# SHIELDV1_NANO.net
KiCad netlist of a schematic drawn in EAGLE
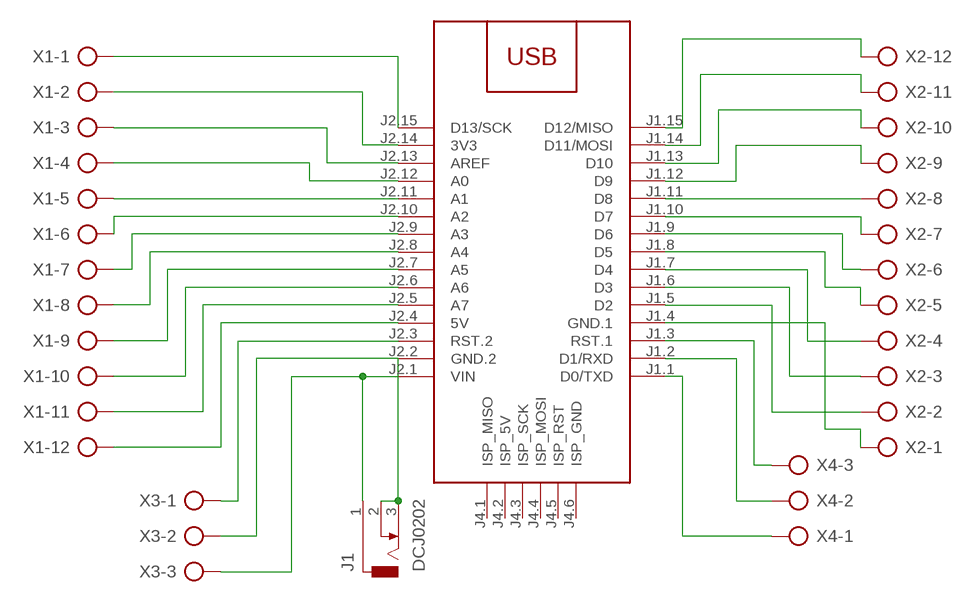
[diagram p0: schematic, sheet 1]

(export (version "E")
  (design (tool "Eeschema 10.0.6"))
  (components
    (comp (ref "J1")
      (value "DCJ0202")
      (footprint "eagle-import:DCJ0202")
      (libsource (lib "eagle-import") (part "DCJ0202"))
    )
    (comp (ref "M1")
      (value "ARDUINO-NANO-3.0#ISP")
      (footprint "eagle-import:ARDUINO-NANO-3.0#ISP")
      (libsource (lib "eagle-import") (part "ARDUINO-NANO-3.0#ISP"))
    )
    (comp (ref "X1")
      (value "AK500/12-H")
      (footprint "eagle-import:AK500_12-H")
      (libsource (lib "eagle-import") (part "AK500/12-H"))
    )
    (comp (ref "X2")
      (value "AK500/12-H")
      (footprint "eagle-import:AK500_12-H")
      (libsource (lib "eagle-import") (part "AK500/12-H"))
    )
    (comp (ref "X3")
      (value "AK500/3")
      (footprint "eagle-import:AK500_3")
      (libsource (lib "eagle-import") (part "AK500/3"))
    )
    (comp (ref "X4")
      (value "AK500/3")
      (footprint "eagle-import:AK500_3")
      (libsource (lib "eagle-import") (part "AK500/3"))
    )
  )
  (nets
    (net (code "1") (name "Net-(M1-3V3)") (class "Default")
      (node (ref "M1") (pin "J2.14") (pinfunction "3V3_J2.14") (pintype "power_in"))
      (node (ref "X1") (pin "2") (pinfunction "KL_2") (pintype "passive"))
    )
    (net (code "2") (name "Net-(M1-5V)") (class "Default")
      (node (ref "M1") (pin "J2.4") (pinfunction "5V_J2.4") (pintype "power_in"))
      (node (ref "X1") (pin "12") (pinfunction "KL_12") (pintype "passive"))
    )
    (net (code "3") (name "Net-(M1-A0)") (class "Default")
      (node (ref "M1") (pin "J2.12") (pinfunction "A0_J2.12") (pintype "bidirectional"))
      (node (ref "X1") (pin "4") (pinfunction "KL_4") (pintype "passive"))
    )
    (net (code "4") (name "Net-(M1-A1)") (class "Default")
      (node (ref "M1") (pin "J2.11") (pinfunction "A1_J2.11") (pintype "bidirectional"))
      (node (ref "X1") (pin "5") (pinfunction "KL_5") (pintype "passive"))
    )
    (net (code "5") (name "Net-(M1-A2)") (class "Default")
      (node (ref "M1") (pin "J2.10") (pinfunction "A2_J2.10") (pintype "bidirectional"))
      (node (ref "X1") (pin "6") (pinfunction "KL_6") (pintype "passive"))
    )
    (net (code "6") (name "Net-(M1-A3)") (class "Default")
      (node (ref "M1") (pin "J2.9") (pinfunction "A3_J2.9") (pintype "bidirectional"))
      (node (ref "X1") (pin "7") (pinfunction "KL_7") (pintype "passive"))
    )
    (net (code "7") (name "Net-(M1-A4)") (class "Default")
      (node (ref "M1") (pin "J2.8") (pinfunction "A4_J2.8") (pintype "bidirectional"))
      (node (ref "X1") (pin "8") (pinfunction "KL_8") (pintype "passive"))
    )
    (net (code "8") (name "Net-(M1-A5)") (class "Default")
      (node (ref "M1") (pin "J2.7") (pinfunction "A5_J2.7") (pintype "bidirectional"))
      (node (ref "X1") (pin "9") (pinfunction "KL_9") (pintype "passive"))
    )
    (net (code "9") (name "Net-(M1-A6)") (class "Default")
      (node (ref "M1") (pin "J2.6") (pinfunction "A6_J2.6") (pintype "bidirectional"))
      (node (ref "X1") (pin "10") (pinfunction "KL_10") (pintype "passive"))
    )
    (net (code "10") (name "Net-(M1-A7)") (class "Default")
      (node (ref "M1") (pin "J2.5") (pinfunction "A7_J2.5") (pintype "bidirectional"))
      (node (ref "X1") (pin "11") (pinfunction "KL_11") (pintype "passive"))
    )
    (net (code "11") (name "Net-(M1-AREF)") (class "Default")
      (node (ref "M1") (pin "J2.13") (pinfunction "AREF_J2.13") (pintype "bidirectional"))
      (node (ref "X1") (pin "3") (pinfunction "KL_3") (pintype "passive"))
    )
    (net (code "12") (name "Net-(M1-D0{slash}TXD)") (class "Default")
      (node (ref "M1") (pin "J1.1") (pinfunction "D0/TXD_J1.1") (pintype "bidirectional"))
      (node (ref "X4") (pin "1") (pinfunction "KL_1") (pintype "passive"))
    )
    (net (code "13") (name "Net-(M1-D1{slash}RXD)") (class "Default")
      (node (ref "M1") (pin "J1.2") (pinfunction "D1/RXD_J1.2") (pintype "bidirectional"))
      (node (ref "X4") (pin "2") (pinfunction "KL_2") (pintype "passive"))
    )
    (net (code "14") (name "Net-(M1-D2)") (class "Default")
      (node (ref "M1") (pin "J1.5") (pinfunction "D2_J1.5") (pintype "bidirectional"))
      (node (ref "X2") (pin "2") (pinfunction "KL_2") (pintype "passive"))
    )
    (net (code "15") (name "Net-(M1-D3)") (class "Default")
      (node (ref "M1") (pin "J1.6") (pinfunction "D3_J1.6") (pintype "bidirectional"))
      (node (ref "X2") (pin "3") (pinfunction "KL_3") (pintype "passive"))
    )
    (net (code "16") (name "Net-(M1-D4)") (class "Default")
      (node (ref "M1") (pin "J1.7") (pinfunction "D4_J1.7") (pintype "bidirectional"))
      (node (ref "X2") (pin "4") (pinfunction "KL_4") (pintype "passive"))
    )
    (net (code "17") (name "Net-(M1-D5)") (class "Default")
      (node (ref "M1") (pin "J1.8") (pinfunction "D5_J1.8") (pintype "bidirectional"))
      (node (ref "X2") (pin "5") (pinfunction "KL_5") (pintype "passive"))
    )
    (net (code "18") (name "Net-(M1-D6)") (class "Default")
      (node (ref "M1") (pin "J1.9") (pinfunction "D6_J1.9") (pintype "bidirectional"))
      (node (ref "X2") (pin "6") (pinfunction "KL_6") (pintype "passive"))
    )
    (net (code "19") (name "Net-(M1-D7)") (class "Default")
      (node (ref "M1") (pin "J1.10") (pinfunction "D7_J1.10") (pintype "bidirectional"))
      (node (ref "X2") (pin "7") (pinfunction "KL_7") (pintype "passive"))
    )
    (net (code "20") (name "Net-(M1-D8)") (class "Default")
      (node (ref "M1") (pin "J1.11") (pinfunction "D8_J1.11") (pintype "bidirectional"))
      (node (ref "X2") (pin "8") (pinfunction "KL_8") (pintype "passive"))
    )
    (net (code "21") (name "Net-(M1-D9)") (class "Default")
      (node (ref "M1") (pin "J1.12") (pinfunction "D9_J1.12") (pintype "bidirectional"))
      (node (ref "X2") (pin "9") (pinfunction "KL_9") (pintype "passive"))
    )
    (net (code "22") (name "Net-(M1-D10)") (class "Default")
      (node (ref "M1") (pin "J1.13") (pinfunction "D10_J1.13") (pintype "bidirectional"))
      (node (ref "X2") (pin "10") (pinfunction "KL_10") (pintype "passive"))
    )
    (net (code "23") (name "Net-(M1-D11{slash}MOSI)") (class "Default")
      (node (ref "M1") (pin "J1.14") (pinfunction "D11/MOSI_J1.14") (pintype "bidirectional"))
      (node (ref "X2") (pin "11") (pinfunction "KL_11") (pintype "passive"))
    )
    (net (code "24") (name "Net-(M1-D12{slash}MISO)") (class "Default")
      (node (ref "M1") (pin "J1.15") (pinfunction "D12/MISO_J1.15") (pintype "bidirectional"))
      (node (ref "X2") (pin "12") (pinfunction "KL_12") (pintype "passive"))
    )
    (net (code "25") (name "Net-(M1-D13{slash}SCK)") (class "Default")
      (node (ref "M1") (pin "J2.15") (pinfunction "D13/SCK_J2.15") (pintype "bidirectional"))
      (node (ref "X1") (pin "1") (pinfunction "KL_1") (pintype "passive"))
    )
    (net (code "26") (name "Net-(M1-GND.1)") (class "Default")
      (node (ref "M1") (pin "J1.4") (pinfunction "GND.1_J1.4") (pintype "power_in"))
      (node (ref "X2") (pin "1") (pinfunction "KL_1") (pintype "passive"))
    )
    (net (code "27") (name "Net-(M1-GND.2)") (class "Default")
      (node (ref "J1") (pin "2") (pinfunction "2_2") (pintype "passive"))
      (node (ref "J1") (pin "3") (pinfunction "3_3") (pintype "passive"))
      (node (ref "M1") (pin "J2.2") (pinfunction "GND.2_J2.2") (pintype "power_in"))
      (node (ref "X3") (pin "2") (pinfunction "KL_2") (pintype "passive"))
    )
    (net (code "28") (name "Net-(M1-RST.1)") (class "Default")
      (node (ref "M1") (pin "J1.3") (pinfunction "RST.1_J1.3") (pintype "bidirectional"))
      (node (ref "X4") (pin "3") (pinfunction "KL_3") (pintype "passive"))
    )
    (net (code "29") (name "Net-(M1-RST.2)") (class "Default")
      (node (ref "M1") (pin "J2.3") (pinfunction "RST.2_J2.3") (pintype "bidirectional"))
      (node (ref "X3") (pin "1") (pinfunction "KL_1") (pintype "passive"))
    )
    (net (code "30") (name "Net-(M1-VIN)") (class "Default")
      (node (ref "J1") (pin "1") (pinfunction "1_1") (pintype "passive"))
      (node (ref "M1") (pin "J2.1") (pinfunction "VIN_J2.1") (pintype "power_in"))
      (node (ref "X3") (pin "3") (pinfunction "KL_3") (pintype "passive"))
    )
    (net (code "31") (name "unconnected-(M1-ISP_5V-PadJ4.2)") (class "Default")
      (node (ref "M1") (pin "J4.2") (pinfunction "ISP_5V_J4.2") (pintype "bidirectional"))
    )
    (net (code "32") (name "unconnected-(M1-ISP_GND-PadJ4.6)") (class "Default")
      (node (ref "M1") (pin "J4.6") (pinfunction "ISP_GND_J4.6") (pintype "bidirectional"))
    )
    (net (code "33") (name "unconnected-(M1-ISP_MISO-PadJ4.1)") (class "Default")
      (node (ref "M1") (pin "J4.1") (pinfunction "ISP_MISO_J4.1") (pintype "bidirectional"))
    )
    (net (code "34") (name "unconnected-(M1-ISP_MOSI-PadJ4.4)") (class "Default")
      (node (ref "M1") (pin "J4.4") (pinfunction "ISP_MOSI_J4.4") (pintype "bidirectional"))
    )
    (net (code "35") (name "unconnected-(M1-ISP_RST-PadJ4.5)") (class "Default")
      (node (ref "M1") (pin "J4.5") (pinfunction "ISP_RST_J4.5") (pintype "bidirectional"))
    )
    (net (code "36") (name "unconnected-(M1-ISP_SCK-PadJ4.3)") (class "Default")
      (node (ref "M1") (pin "J4.3") (pinfunction "ISP_SCK_J4.3") (pintype "bidirectional"))
    )
  )
)
